# Side_1_esp32_old.net
KiCad netlist of a schematic drawn in EAGLE
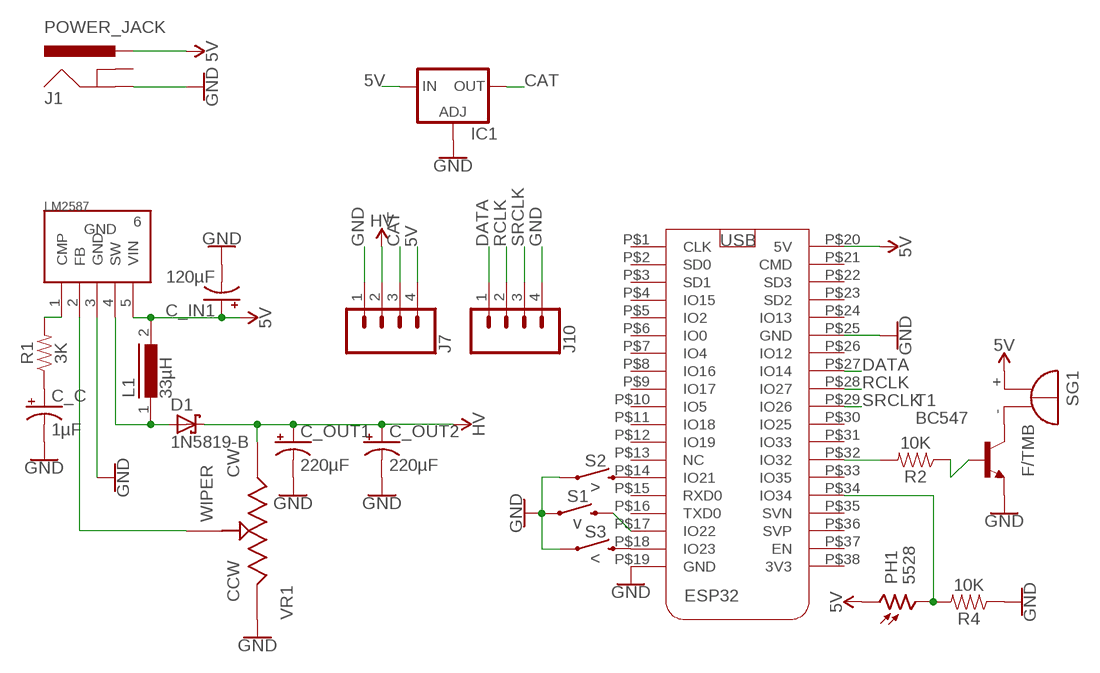
[diagram p0: schematic, sheet 1]

(export (version "E")
  (design (tool "Eeschema 10.0.6"))
  (components
    (comp (ref "C_C")
      (value "1µF")
      (footprint "eagle-import:CAP_POL_2MM")
      (libsource (lib "eagle-import") (part "CAP_POL_1µF"))
    )
    (comp (ref "C_IN1")
      (value "120µF")
      (footprint "eagle-import:CAP_POL_3MM")
      (libsource (lib "eagle-import") (part "CAP_POL_120µF"))
    )
    (comp (ref "C_OUT1")
      (value "220µF")
      (footprint "eagle-import:CPOL-RADIAL-5MM-10MM")
      (libsource (lib "eagle-import") (part "1000UF-RADIAL-5MM-25V-20%"))
    )
    (comp (ref "C_OUT2")
      (value "220µF")
      (footprint "eagle-import:CPOL-RADIAL-5MM-10MM")
      (libsource (lib "eagle-import") (part "1000UF-RADIAL-5MM-25V-20%"))
    )
    (comp (ref "D1")
      (value "1N5819-B")
      (footprint "eagle-import:DO41-7.6")
      (libsource (lib "eagle-import") (part "1N5819-B"))
    )
    (comp (ref "ESP32")
      (value "ESP32_DEVKIT")
      (footprint "eagle-import:ESP32_DEVKIT")
      (libsource (lib "eagle-import") (part "ESP32_DEVKIT"))
    )
    (comp (ref "IC1")
      (value "LM317TS")
      (footprint "eagle-import:317TS")
      (libsource (lib "eagle-import") (part "LM317TS"))
    )
    (comp (ref "J1")
      (value "POWER_JACK")
      (footprint "eagle-import:POWER_JACK_PTH")
      (libsource (lib "eagle-import") (part "POWER_JACK"))
    )
    (comp (ref "J7")
      (value "CONN_04")
      (footprint "eagle-import:1X04")
      (libsource (lib "eagle-import") (part "CONN_04"))
    )
    (comp (ref "J10")
      (value "CONN_04")
      (footprint "eagle-import:1X04")
      (libsource (lib "eagle-import") (part "CONN_04"))
    )
    (comp (ref "L1")
      (value "33µH")
      (footprint "eagle-import:MICC12")
      (libsource (lib "eagle-import") (part "MICC12"))
    )
    (comp (ref "LM2587")
      (value "LM2587S")
      (footprint "eagle-import:TO263-5")
      (libsource (lib "eagle-import") (part "LM2587S"))
    )
    (comp (ref "PH1")
      (value "5528")
      (footprint "eagle-import:5528")
      (libsource (lib "eagle-import") (part "5528"))
    )
    (comp (ref "R1")
      (value "3K")
      (footprint "eagle-import:AXIAL-0.3")
      (libsource (lib "eagle-import") (part "RESISTORAXIAL-0.3"))
    )
    (comp (ref "R2")
      (value "10K")
      (footprint "eagle-import:AXIAL-0.3")
      (libsource (lib "eagle-import") (part "RESISTORAXIAL-0.3"))
    )
    (comp (ref "R4")
      (value "10K")
      (footprint "eagle-import:AXIAL-0.3")
      (libsource (lib "eagle-import") (part "RESISTORAXIAL-0.3"))
    )
    (comp (ref "S1")
      (value "v")
      (footprint "eagle-import:TACTILE_SWITCH_PTH_6.0MM")
      (libsource (lib "eagle-import") (part "MOMENTARY-SWITCH-SPST-PTH-6.0MM"))
    )
    (comp (ref "S2")
      (value ">")
      (footprint "eagle-import:TACTILE_SWITCH_PTH_6.0MM")
      (libsource (lib "eagle-import") (part "MOMENTARY-SWITCH-SPST-PTH-6.0MM"))
    )
    (comp (ref "S3")
      (value "<")
      (footprint "eagle-import:TACTILE_SWITCH_PTH_6.0MM")
      (libsource (lib "eagle-import") (part "MOMENTARY-SWITCH-SPST-PTH-6.0MM"))
    )
    (comp (ref "SG1")
      (value "F/TMB")
      (footprint "eagle-import:F_TMB")
      (libsource (lib "eagle-import") (part "F/TMB"))
    )
    (comp (ref "T1")
      (value "BC547")
      (footprint "eagle-import:TO92")
      (libsource (lib "eagle-import") (part "BC547"))
    )
    (comp (ref "VR1")
      (value "3296W-1-103LF")
      (footprint "eagle-import:W")
      (fields
        (field (name "MANUFACTURER") "Bourns Inc")
        (field (name "POWER") "0.5W, 1/2W")
        (field (name "TOLERANCE") "10%")
      )
      (libsource (lib "eagle-import") (part "3296?-W1-103LF"))
    )
  )
  (nets
    (net (code "1") (name "/CAT") (class "Default")
      (node (ref "IC1") (pin "2") (pinfunction "OUT_2") (pintype "passive"))
      (node (ref "J7") (pin "3") (pinfunction "3_3") (pintype "passive"))
    )
    (net (code "2") (name "/DATA") (class "Default")
      (node (ref "ESP32") (pin "P$27") (pinfunction "IO14_P$27") (pintype "bidirectional"))
      (node (ref "J10") (pin "1") (pinfunction "1_1") (pintype "passive"))
    )
    (net (code "3") (name "/RCLK") (class "Default")
      (node (ref "ESP32") (pin "P$28") (pinfunction "IO27_P$28") (pintype "bidirectional"))
      (node (ref "J10") (pin "2") (pinfunction "2_2") (pintype "passive"))
    )
    (net (code "4") (name "/SRCLK") (class "Default")
      (node (ref "ESP32") (pin "P$29") (pinfunction "IO26_P$29") (pintype "bidirectional"))
      (node (ref "J10") (pin "3") (pinfunction "3_3") (pintype "passive"))
    )
    (net (code "5") (name "5V") (class "Default")
      (node (ref "C_IN1") (pin "POS") (pinfunction "+_POS") (pintype "passive"))
      (node (ref "ESP32") (pin "P$20") (pinfunction "5V_P$20") (pintype "bidirectional"))
      (node (ref "IC1") (pin "3") (pinfunction "IN_3") (pintype "input"))
      (node (ref "J1") (pin "PWR") (pinfunction "PWR_PWR") (pintype "bidirectional"))
      (node (ref "J7") (pin "4") (pinfunction "4_4") (pintype "passive"))
      (node (ref "L1") (pin "2") (pinfunction "2_2") (pintype "passive"))
      (node (ref "LM2587") (pin "5") (pinfunction "VIN_5") (pintype "bidirectional"))
      (node (ref "PH1") (pin "1") (pinfunction "1_1") (pintype "passive"))
      (node (ref "SG1") (pin "+") (pinfunction "+_+") (pintype "passive"))
    )
    (net (code "6") (name "GND") (class "Default")
      (node (ref "C_C") (pin "NEG") (pinfunction "-_NEG") (pintype "passive"))
      (node (ref "C_IN1") (pin "NEG") (pinfunction "-_NEG") (pintype "passive"))
      (node (ref "C_OUT1") (pin "-") (pinfunction "-_-") (pintype "passive"))
      (node (ref "C_OUT2") (pin "-") (pinfunction "-_-") (pintype "passive"))
      (node (ref "ESP32") (pin "P$19") (pinfunction "GND_P$19") (pintype "bidirectional"))
      (node (ref "ESP32") (pin "P$25") (pinfunction "GND_P$25") (pintype "bidirectional"))
      (node (ref "IC1") (pin "1") (pinfunction "ADJ_1") (pintype "input"))
      (node (ref "J1") (pin "GND") (pinfunction "GND_GND") (pintype "bidirectional"))
      (node (ref "J10") (pin "4") (pinfunction "4_4") (pintype "passive"))
      (node (ref "J7") (pin "1") (pinfunction "1_1") (pintype "passive"))
      (node (ref "LM2587") (pin "3") (pinfunction "GND_3") (pintype "bidirectional"))
      (node (ref "R4") (pin "P$1") (pinfunction "1_P$1") (pintype "passive"))
      (node (ref "S1") (pin "1") (pinfunction "1_1") (pintype "passive"))
      (node (ref "S2") (pin "1") (pinfunction "1_1") (pintype "passive"))
      (node (ref "S3") (pin "1") (pinfunction "1_1") (pintype "passive"))
      (node (ref "T1") (pin "1") (pinfunction "E_1") (pintype "passive"))
      (node (ref "VR1") (pin "1") (pinfunction "1_1") (pintype "passive"))
    )
    (net (code "7") (name "HV") (class "Default")
      (node (ref "C_OUT1") (pin "+") (pinfunction "+_+") (pintype "passive"))
      (node (ref "C_OUT2") (pin "+") (pinfunction "+_+") (pintype "passive"))
      (node (ref "D1") (pin "C") (pinfunction "C_C") (pintype "passive"))
      (node (ref "J7") (pin "2") (pinfunction "2_2") (pintype "passive"))
      (node (ref "VR1") (pin "3") (pinfunction "3_3") (pintype "passive"))
    )
    (net (code "8") (name "Net-(C_C-+)") (class "Default")
      (node (ref "C_C") (pin "POS") (pinfunction "+_POS") (pintype "passive"))
      (node (ref "R1") (pin "P$1") (pinfunction "1_P$1") (pintype "passive"))
    )
    (net (code "9") (name "Net-(ESP32-IO21)") (class "Default")
      (node (ref "ESP32") (pin "P$14") (pinfunction "IO21_P$14") (pintype "bidirectional"))
      (node (ref "S2") (pin "3") (pinfunction "2_3") (pintype "passive"))
    )
    (net (code "10") (name "Net-(ESP32-IO22)") (class "Default")
      (node (ref "ESP32") (pin "P$17") (pinfunction "IO22_P$17") (pintype "bidirectional"))
      (node (ref "S1") (pin "3") (pinfunction "2_3") (pintype "passive"))
    )
    (net (code "11") (name "Net-(ESP32-IO23)") (class "Default")
      (node (ref "ESP32") (pin "P$18") (pinfunction "IO23_P$18") (pintype "bidirectional"))
      (node (ref "S3") (pin "3") (pinfunction "2_3") (pintype "passive"))
    )
    (net (code "12") (name "Net-(ESP32-IO32)") (class "Default")
      (node (ref "ESP32") (pin "P$32") (pinfunction "IO32_P$32") (pintype "bidirectional"))
      (node (ref "R2") (pin "P$2") (pinfunction "2_P$2") (pintype "passive"))
    )
    (net (code "13") (name "Net-(ESP32-IO34)") (class "Default")
      (node (ref "ESP32") (pin "P$34") (pinfunction "IO34_P$34") (pintype "bidirectional"))
      (node (ref "PH1") (pin "2") (pinfunction "2_2") (pintype "passive"))
      (node (ref "R4") (pin "P$2") (pinfunction "2_P$2") (pintype "passive"))
    )
    (net (code "14") (name "Net-(LM2587-CMP)") (class "Default")
      (node (ref "LM2587") (pin "1") (pinfunction "CMP_1") (pintype "bidirectional"))
      (node (ref "R1") (pin "P$2") (pinfunction "2_P$2") (pintype "passive"))
    )
    (net (code "15") (name "Net-(LM2587-FB)") (class "Default")
      (node (ref "LM2587") (pin "2") (pinfunction "FB_2") (pintype "bidirectional"))
      (node (ref "VR1") (pin "2") (pinfunction "2_2") (pintype "passive"))
    )
    (net (code "16") (name "Net-(LM2587-SW)") (class "Default")
      (node (ref "D1") (pin "A") (pinfunction "A_A") (pintype "passive"))
      (node (ref "L1") (pin "1") (pinfunction "1_1") (pintype "passive"))
      (node (ref "LM2587") (pin "4") (pinfunction "SW_4") (pintype "bidirectional"))
    )
    (net (code "17") (name "Net-(R2-1)") (class "Default")
      (node (ref "R2") (pin "P$1") (pinfunction "1_P$1") (pintype "passive"))
      (node (ref "T1") (pin "2") (pinfunction "B_2") (pintype "passive"))
    )
    (net (code "18") (name "Net-(T1-C)") (class "Default")
      (node (ref "SG1") (pin "-") (pinfunction "-_-") (pintype "passive"))
      (node (ref "T1") (pin "3") (pinfunction "C_3") (pintype "passive"))
    )
    (net (code "19") (name "unconnected-(ESP32-3V3-PadP$38)") (class "Default")
      (node (ref "ESP32") (pin "P$38") (pinfunction "3V3_P$38") (pintype "bidirectional"))
    )
    (net (code "20") (name "unconnected-(ESP32-CLK-PadP$1)") (class "Default")
      (node (ref "ESP32") (pin "P$1") (pinfunction "CLK_P$1") (pintype "bidirectional"))
    )
    (net (code "21") (name "unconnected-(ESP32-CMD-PadP$21)") (class "Default")
      (node (ref "ESP32") (pin "P$21") (pinfunction "CMD_P$21") (pintype "bidirectional"))
    )
    (net (code "22") (name "unconnected-(ESP32-EN-PadP$37)") (class "Default")
      (node (ref "ESP32") (pin "P$37") (pinfunction "EN_P$37") (pintype "bidirectional"))
    )
    (net (code "23") (name "unconnected-(ESP32-IO0-PadP$6)") (class "Default")
      (node (ref "ESP32") (pin "P$6") (pinfunction "IO0_P$6") (pintype "bidirectional"))
    )
    (net (code "24") (name "unconnected-(ESP32-IO2-PadP$5)") (class "Default")
      (node (ref "ESP32") (pin "P$5") (pinfunction "IO2_P$5") (pintype "bidirectional"))
    )
    (net (code "25") (name "unconnected-(ESP32-IO4-PadP$7)") (class "Default")
      (node (ref "ESP32") (pin "P$7") (pinfunction "IO4_P$7") (pintype "bidirectional"))
    )
    (net (code "26") (name "unconnected-(ESP32-IO5-PadP$10)") (class "Default")
      (node (ref "ESP32") (pin "P$10") (pinfunction "IO5_P$10") (pintype "bidirectional"))
    )
    (net (code "27") (name "unconnected-(ESP32-IO12-PadP$26)") (class "Default")
      (node (ref "ESP32") (pin "P$26") (pinfunction "IO12_P$26") (pintype "bidirectional"))
    )
    (net (code "28") (name "unconnected-(ESP32-IO13-PadP$24)") (class "Default")
      (node (ref "ESP32") (pin "P$24") (pinfunction "IO13_P$24") (pintype "bidirectional"))
    )
    (net (code "29") (name "unconnected-(ESP32-IO15-PadP$4)") (class "Default")
      (node (ref "ESP32") (pin "P$4") (pinfunction "IO15_P$4") (pintype "bidirectional"))
    )
    (net (code "30") (name "unconnected-(ESP32-IO16-PadP$8)") (class "Default")
      (node (ref "ESP32") (pin "P$8") (pinfunction "IO16_P$8") (pintype "bidirectional"))
    )
    (net (code "31") (name "unconnected-(ESP32-IO17-PadP$9)") (class "Default")
      (node (ref "ESP32") (pin "P$9") (pinfunction "IO17_P$9") (pintype "bidirectional"))
    )
    (net (code "32") (name "unconnected-(ESP32-IO18-PadP$11)") (class "Default")
      (node (ref "ESP32") (pin "P$11") (pinfunction "IO18_P$11") (pintype "bidirectional"))
    )
    (net (code "33") (name "unconnected-(ESP32-IO19-PadP$12)") (class "Default")
      (node (ref "ESP32") (pin "P$12") (pinfunction "IO19_P$12") (pintype "bidirectional"))
    )
    (net (code "34") (name "unconnected-(ESP32-IO25-PadP$30)") (class "Default")
      (node (ref "ESP32") (pin "P$30") (pinfunction "IO25_P$30") (pintype "bidirectional"))
    )
    (net (code "35") (name "unconnected-(ESP32-IO33-PadP$31)") (class "Default")
      (node (ref "ESP32") (pin "P$31") (pinfunction "IO33_P$31") (pintype "bidirectional"))
    )
    (net (code "36") (name "unconnected-(ESP32-IO35-PadP$33)") (class "Default")
      (node (ref "ESP32") (pin "P$33") (pinfunction "IO35_P$33") (pintype "bidirectional"))
    )
    (net (code "37") (name "unconnected-(ESP32-NC-PadP$13)") (class "Default")
      (node (ref "ESP32") (pin "P$13") (pinfunction "NC_P$13") (pintype "bidirectional"))
    )
    (net (code "38") (name "unconnected-(ESP32-RXD0-PadP$15)") (class "Default")
      (node (ref "ESP32") (pin "P$15") (pinfunction "RXD0_P$15") (pintype "bidirectional"))
    )
    (net (code "39") (name "unconnected-(ESP32-SD0-PadP$2)") (class "Default")
      (node (ref "ESP32") (pin "P$2") (pinfunction "SD0_P$2") (pintype "bidirectional"))
    )
    (net (code "40") (name "unconnected-(ESP32-SD1-PadP$3)") (class "Default")
      (node (ref "ESP32") (pin "P$3") (pinfunction "SD1_P$3") (pintype "bidirectional"))
    )
    (net (code "41") (name "unconnected-(ESP32-SD2-PadP$23)") (class "Default")
      (node (ref "ESP32") (pin "P$23") (pinfunction "SD2_P$23") (pintype "bidirectional"))
    )
    (net (code "42") (name "unconnected-(ESP32-SD3-PadP$22)") (class "Default")
      (node (ref "ESP32") (pin "P$22") (pinfunction "SD3_P$22") (pintype "bidirectional"))
    )
    (net (code "43") (name "unconnected-(ESP32-SVN-PadP$35)") (class "Default")
      (node (ref "ESP32") (pin "P$35") (pinfunction "SVN_P$35") (pintype "bidirectional"))
    )
    (net (code "44") (name "unconnected-(ESP32-SVP-PadP$36)") (class "Default")
      (node (ref "ESP32") (pin "P$36") (pinfunction "SVP_P$36") (pintype "bidirectional"))
    )
    (net (code "45") (name "unconnected-(ESP32-TXD0-PadP$16)") (class "Default")
      (node (ref "ESP32") (pin "P$16") (pinfunction "TXD0_P$16") (pintype "bidirectional"))
    )
    (net (code "46") (name "unconnected-(J1-PadGNDBREAK)") (class "Default")
      (node (ref "J1") (pin "GNDBREAK") (pinfunction "GNDBREAK_GNDBREAK") (pintype "bidirectional"))
    )
    (net (code "47") (name "unconnected-(LM2587-GND-Pad6)") (class "Default")
      (node (ref "LM2587") (pin "6") (pinfunction "GND_6") (pintype "bidirectional"))
    )
  )
)
